# schematic1.net
KiCad netlist of a schematic drawn in Altium Designer
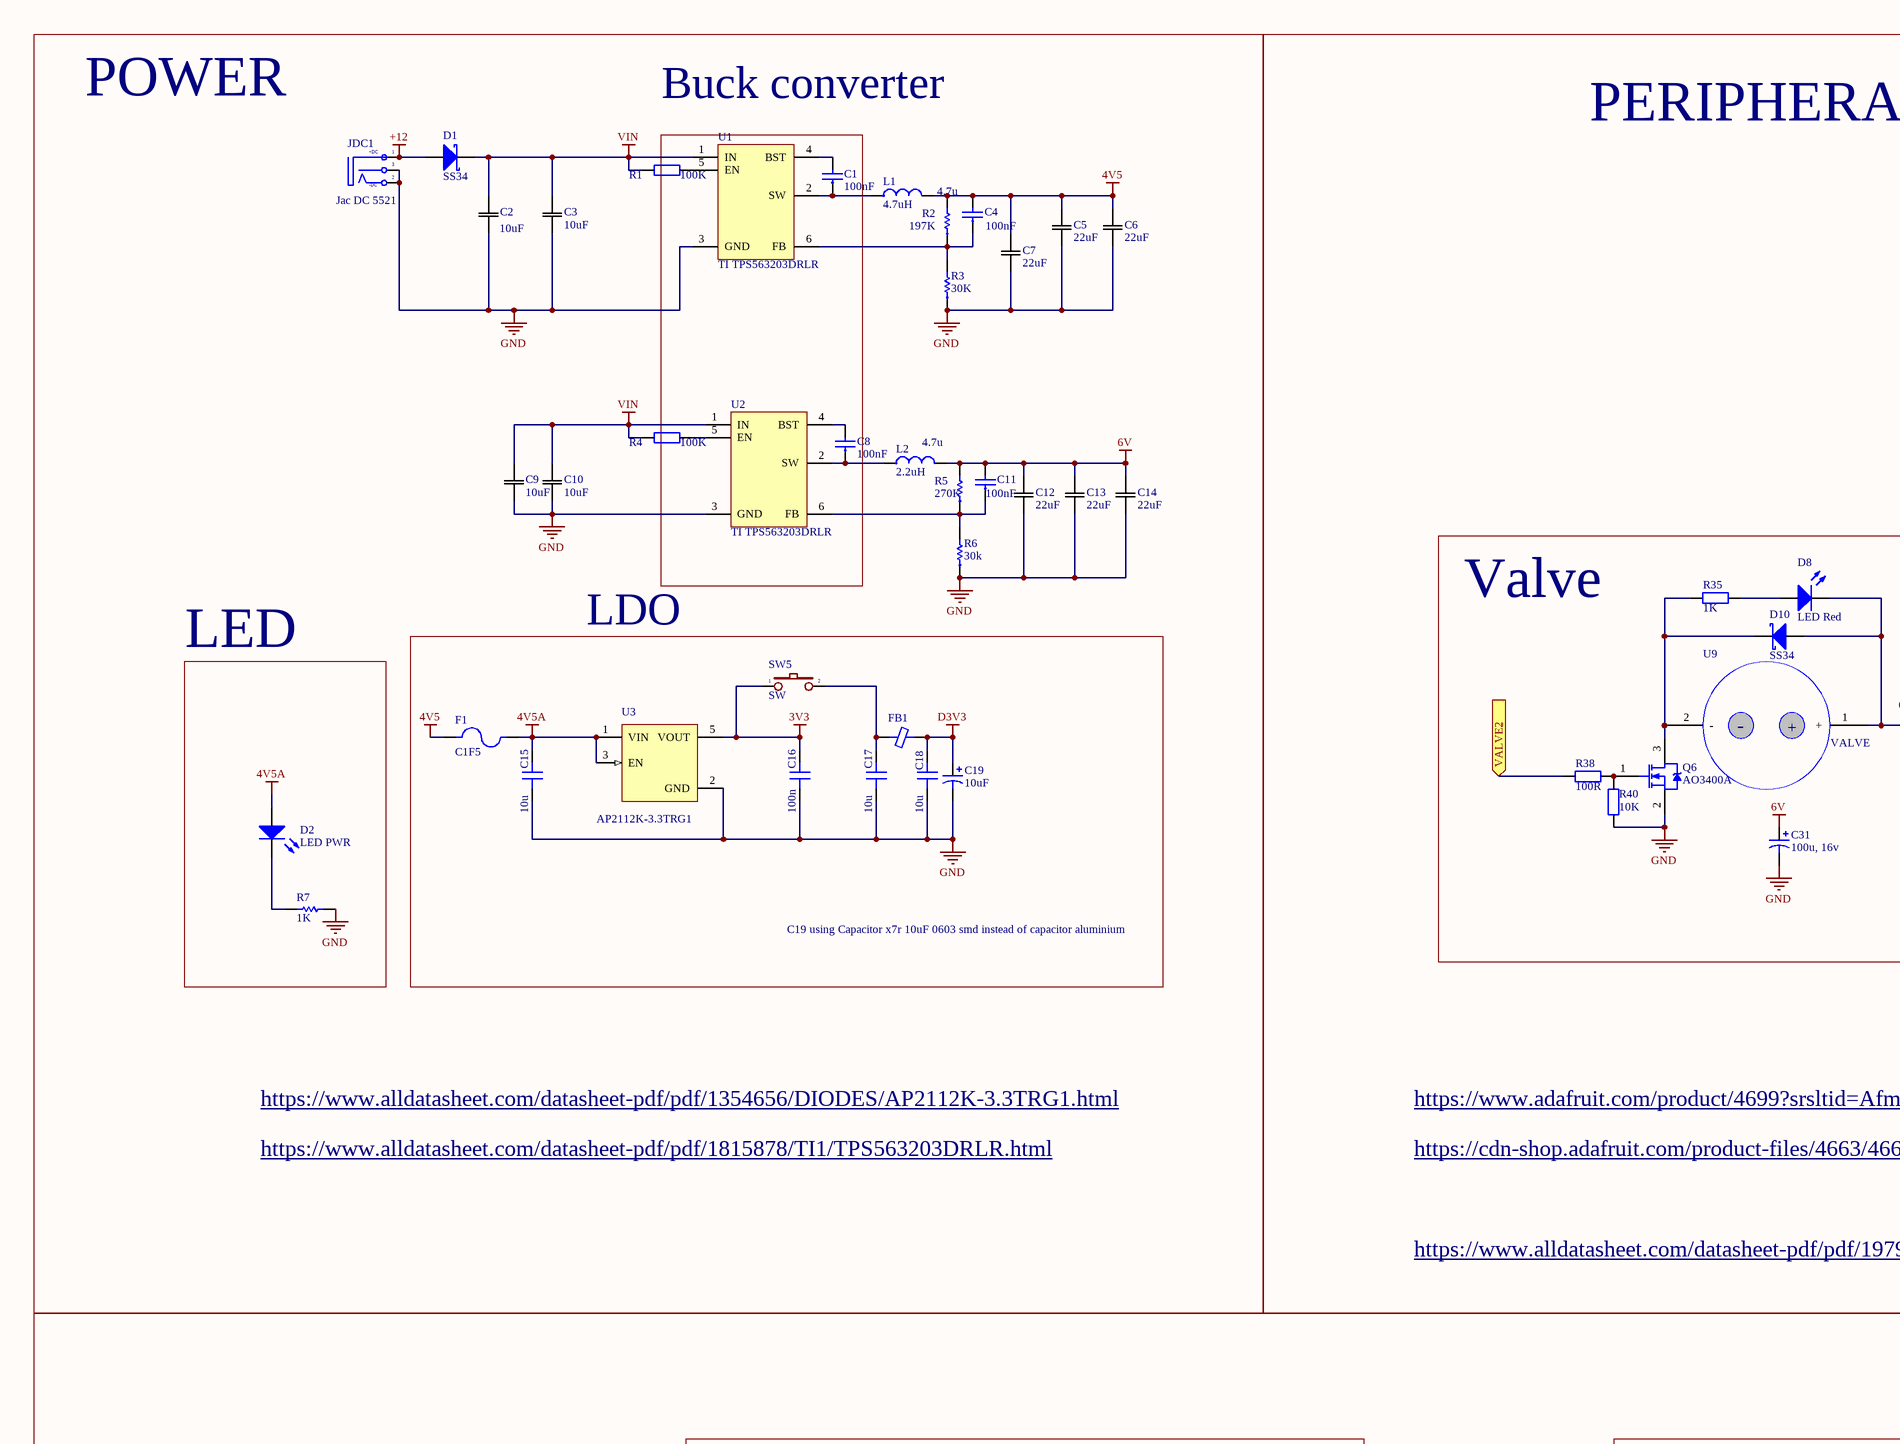
[diagram p0: schematic1.SchDoc, top left]
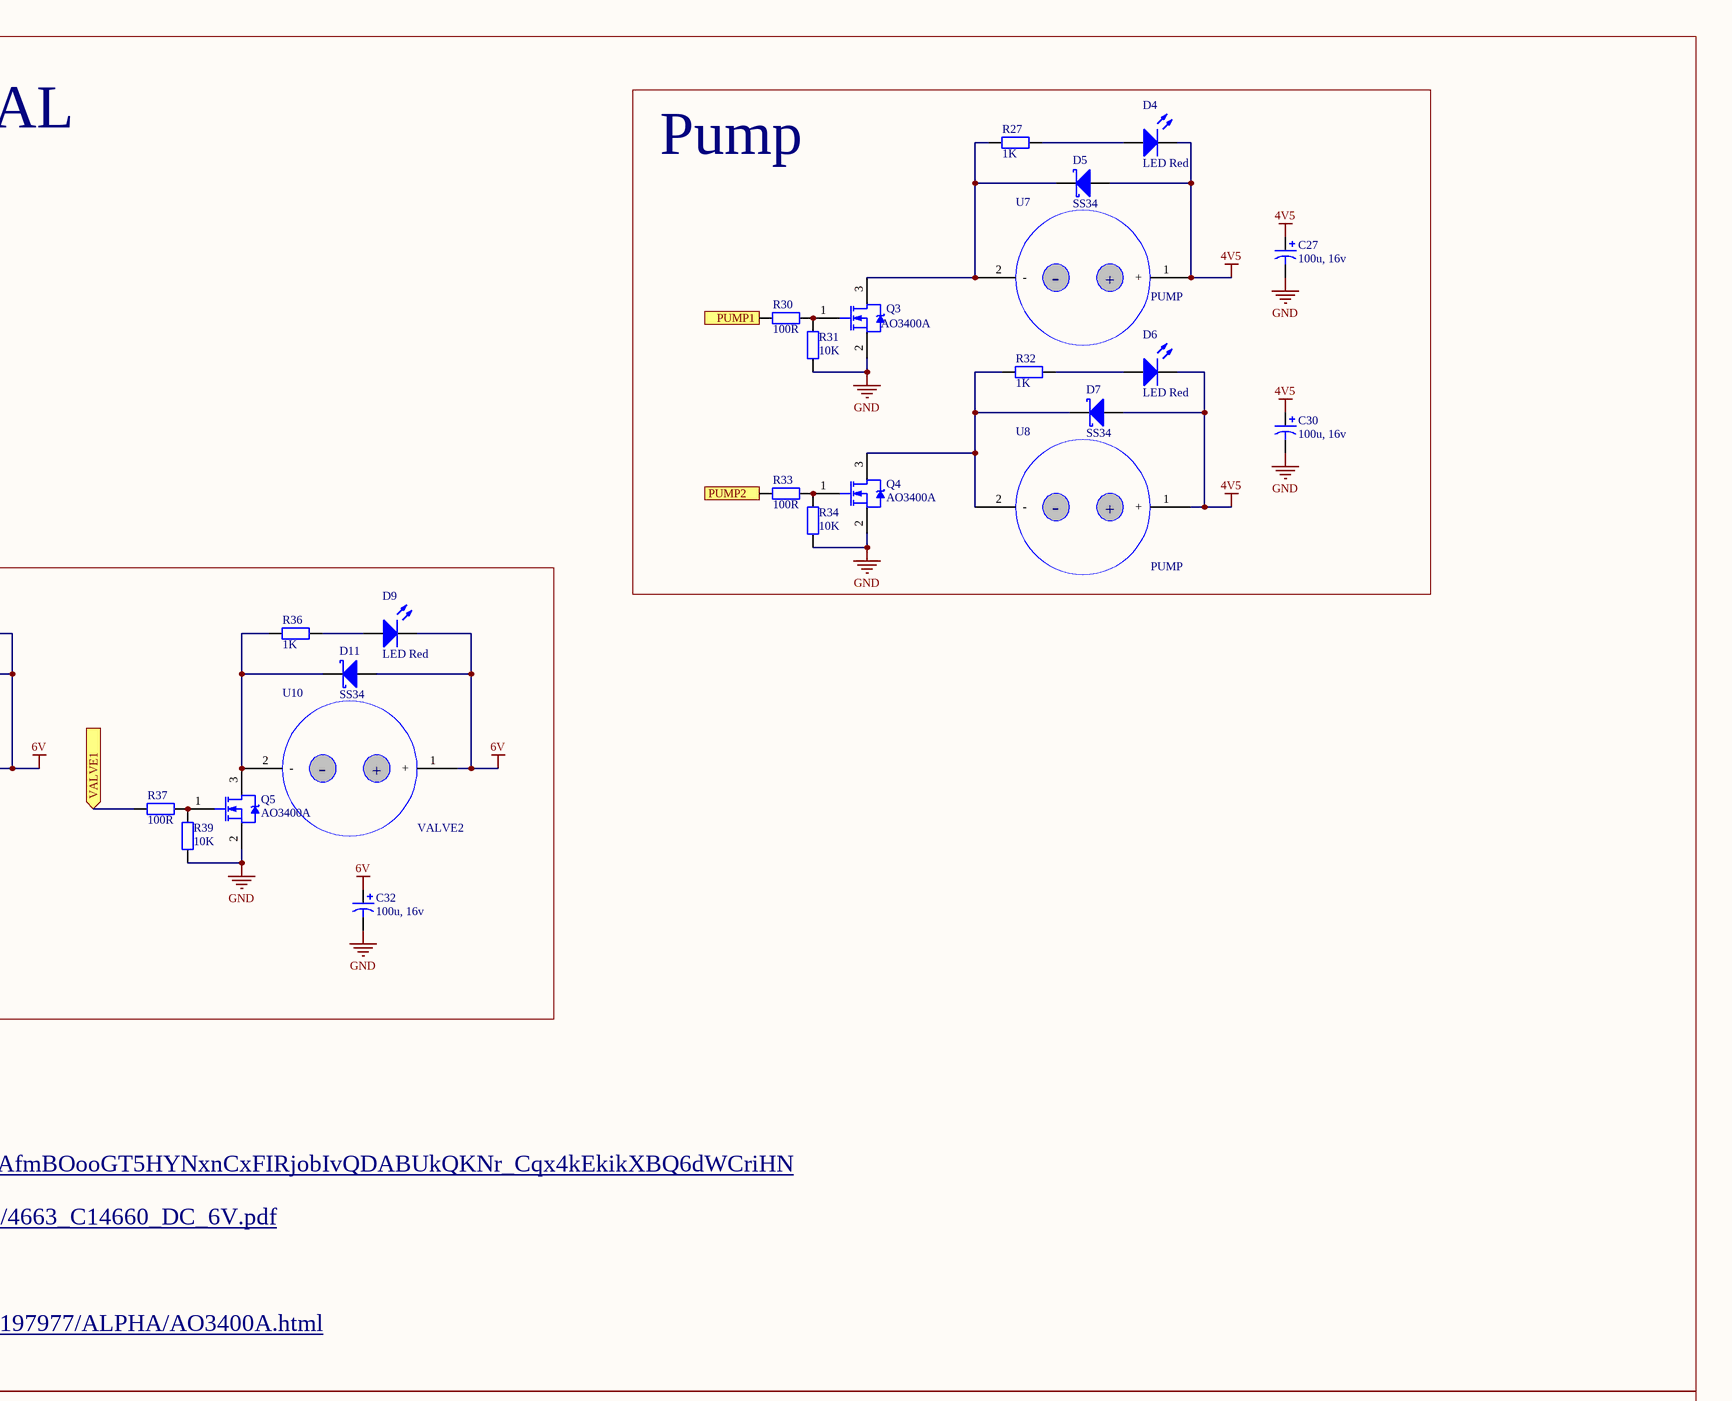
[diagram p1: schematic1.SchDoc, top right]
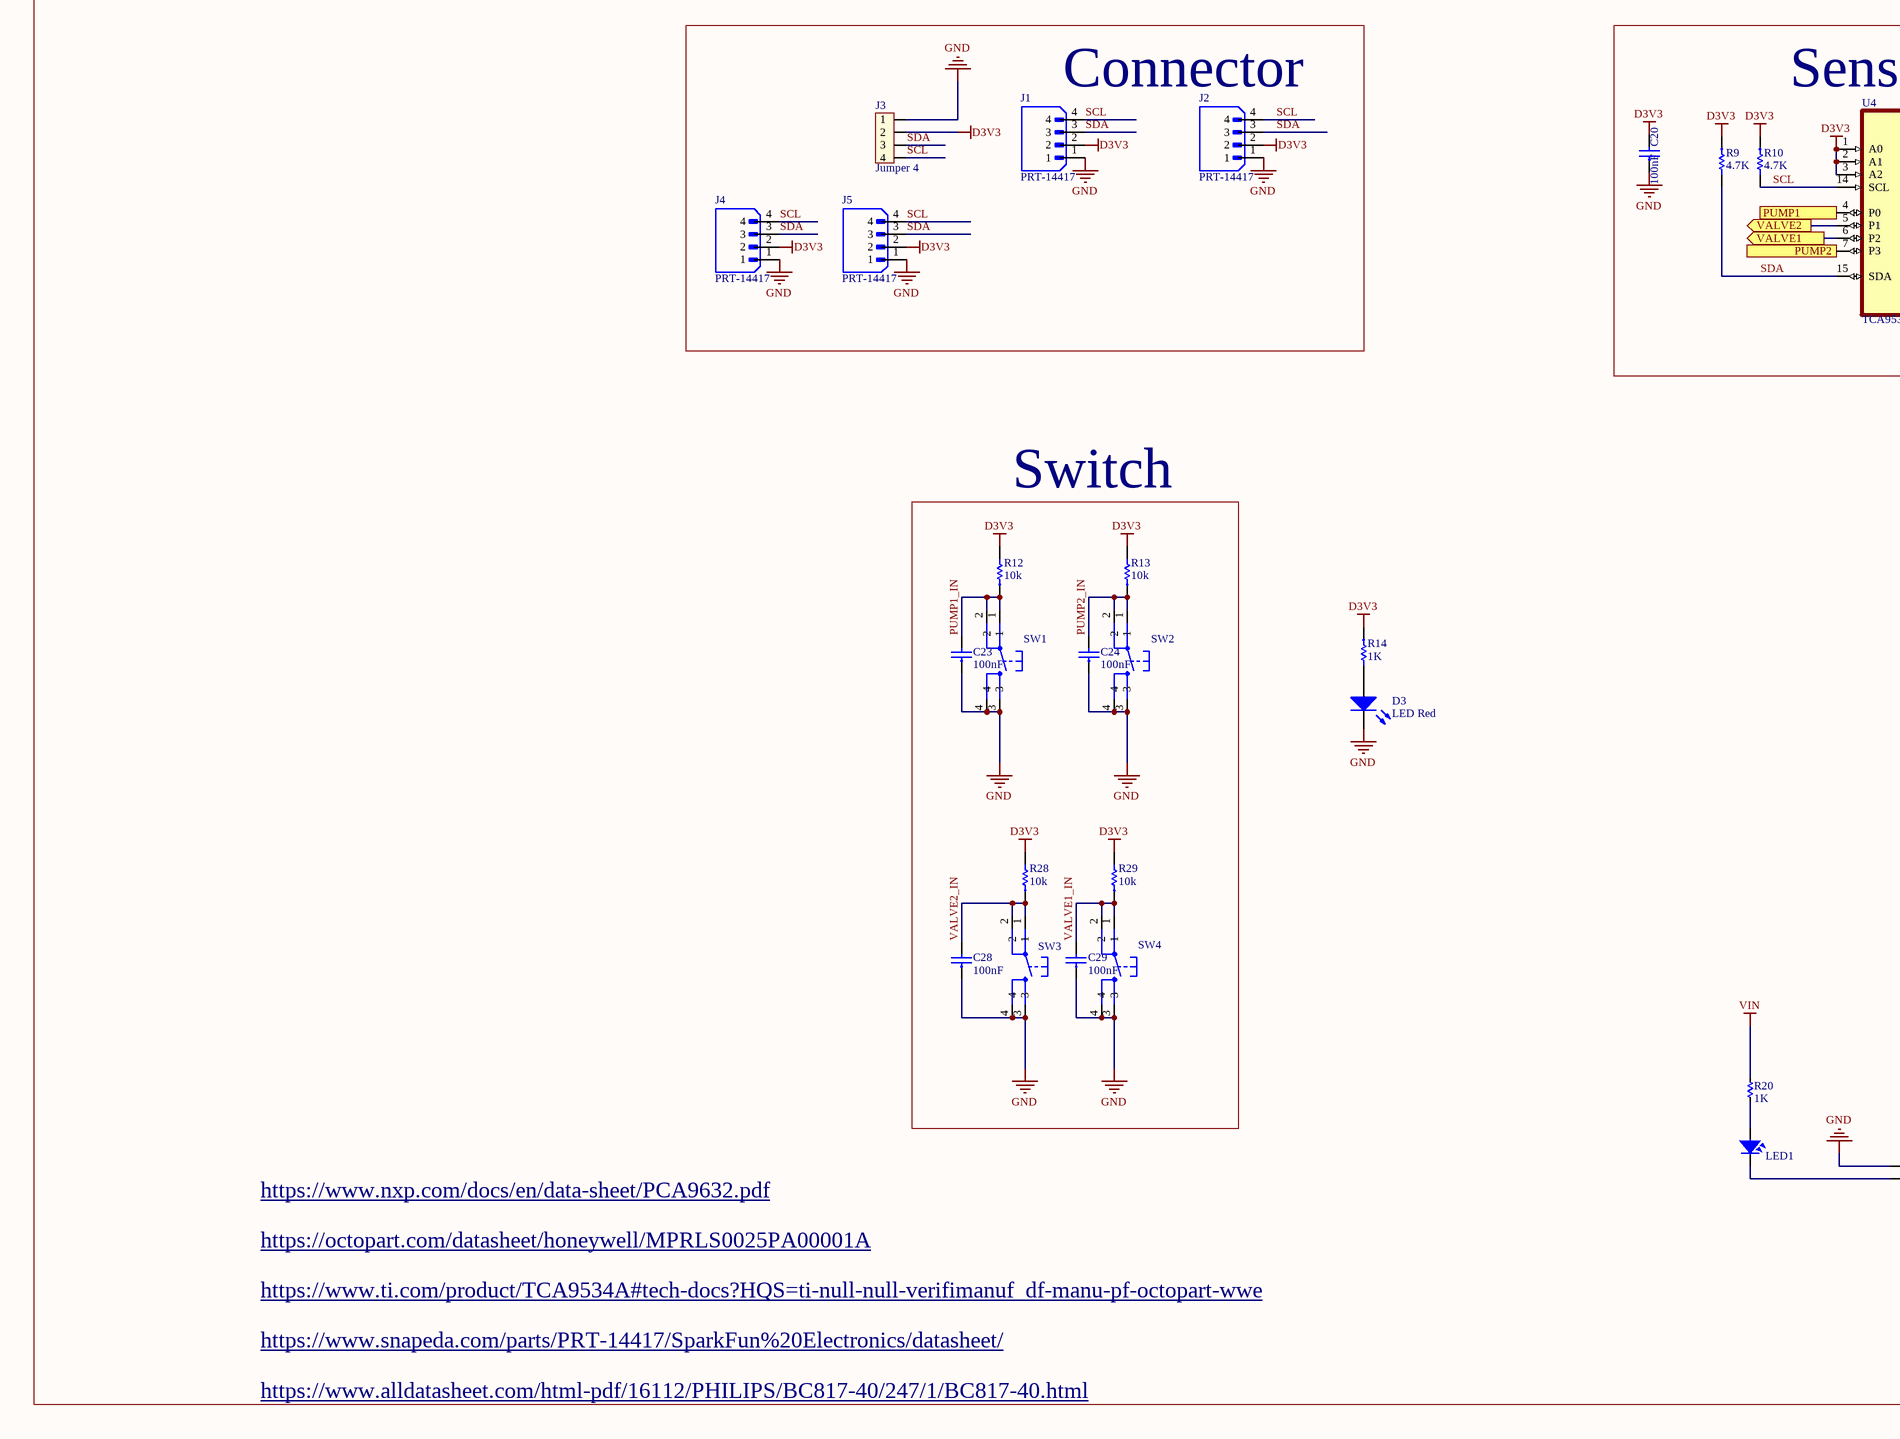
[diagram p2: schematic1.SchDoc, bottom left]
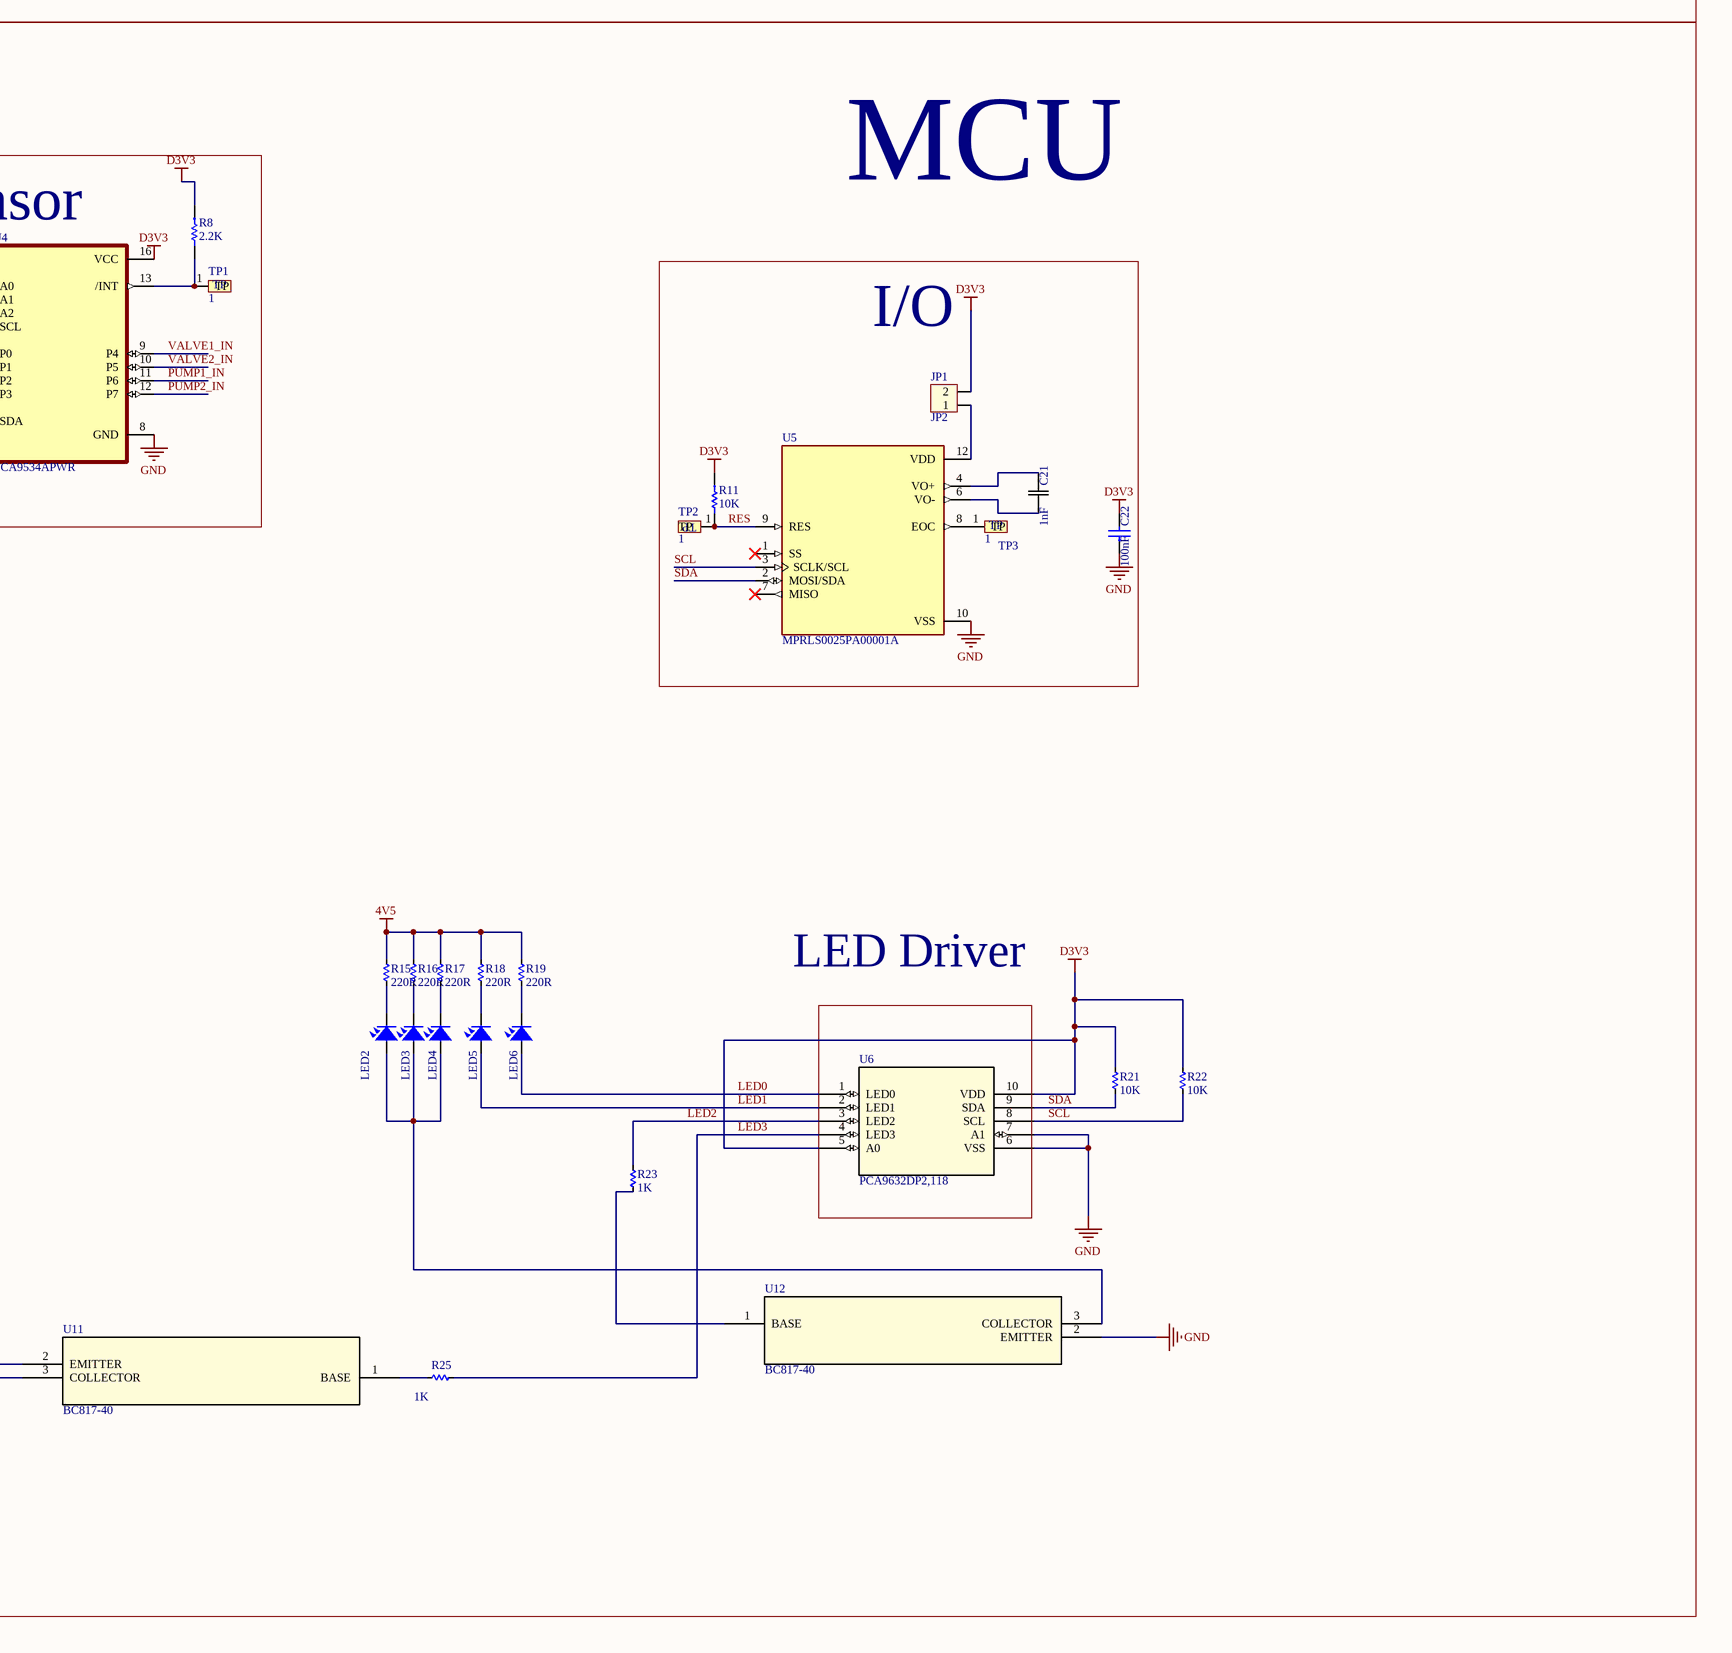
[diagram p3: schematic1.SchDoc, bottom right]

(export (version "E")
  (design (tool "Eeschema 10.0.6"))
  (components
    (comp (ref "C1")
      (value "100nF")
      (footprint "CN-SMD-0603")
      (description "CAP CER 100nF 10% 50V X7R 0603 SMD")
      (libsource (lib "2502-GMQLITE-MAIN") (part "CAPCER0001 100nF 10% 50V X7R 0603 SMD_1"))
    )
    (comp (ref "C2")
      (value "10uF")
      (footprint "CL10A106MQ8NNNC:CAP_CL10_SAM")
      (description "Description")
      (fields
        (field (name "MANUFACTURER_PART_NUMBER") "CL10A106MQ8NNNC")
        (field (name "COPYRIGHT") "Copyright (C) 2026 Ultra Librarian. All rights reserved.")
      )
      (libsource (lib "CL10A106MQ8NNNC") (part "CL10A106MQ8NNNC"))
    )
    (comp (ref "C3")
      (value "10uF")
      (footprint "CL10A106MQ8NNNC:CAP_CL10_SAM")
      (description "Description")
      (fields
        (field (name "MANUFACTURER_PART_NUMBER") "CL10A106MQ8NNNC")
        (field (name "COPYRIGHT") "Copyright (C) 2026 Ultra Librarian. All rights reserved.")
      )
      (libsource (lib "CL10A106MQ8NNNC") (part "CL10A106MQ8NNNC"))
    )
    (comp (ref "C4")
      (value "100nF")
      (footprint "CN-SMD-0603")
      (description "CAP CER 100nF 10% 50V X7R 0603 SMD")
      (libsource (lib "2502-GMQLITE-MAIN") (part "CAPCER0001 100nF 10% 50V X7R 0603 SMD"))
    )
    (comp (ref "C5")
      (value "22uF")
      (footprint "CN-SMD-0603")
      (description "Description")
      (fields
        (field (name "MANUFACTURER_PART_NUMBER") "GRM188R60J226MEA0D")
        (field (name "COPYRIGHT") "Copyright (C) 2026 Ultra Librarian. All rights reserved.")
      )
      (libsource (lib "GRM188R60J226MEA0D") (part "GRM188R60J226MEA0D"))
    )
    (comp (ref "C6")
      (value "22uF")
      (footprint "CN-SMD-0603")
      (description "Description")
      (fields
        (field (name "MANUFACTURER_PART_NUMBER") "GRM188R60J226MEA0D")
        (field (name "COPYRIGHT") "Copyright (C) 2026 Ultra Librarian. All rights reserved.")
      )
      (libsource (lib "GRM188R60J226MEA0D") (part "GRM188R60J226MEA0D"))
    )
    (comp (ref "C7")
      (value "22uF")
      (footprint "CN-SMD-0603")
      (description "Description")
      (fields
        (field (name "MANUFACTURER_PART_NUMBER") "GRM188R60J226MEA0D")
        (field (name "COPYRIGHT") "Copyright (C) 2026 Ultra Librarian. All rights reserved.")
      )
      (libsource (lib "GRM188R60J226MEA0D") (part "GRM188R60J226MEA0D"))
    )
    (comp (ref "C8")
      (value "100nF")
      (footprint "CN-SMD-0603")
      (description "CAP CER 100nF 10% 50V X7R 0603 SMD")
      (libsource (lib "2502-GMQLITE-MAIN") (part "CAPCER0001 100nF 10% 50V X7R 0603 SMD_1"))
    )
    (comp (ref "C9")
      (value "10uF")
      (footprint "CL10A106MQ8NNNC:CAP_CL10_SAM")
      (description "Description")
      (fields
        (field (name "MANUFACTURER_PART_NUMBER") "CL10A106MQ8NNNC")
        (field (name "COPYRIGHT") "Copyright (C) 2026 Ultra Librarian. All rights reserved.")
      )
      (libsource (lib "CL10A106MQ8NNNC") (part "CL10A106MQ8NNNC"))
    )
    (comp (ref "C10")
      (value "10uF")
      (footprint "CL10A106MQ8NNNC:CAP_CL10_SAM")
      (description "Description")
      (fields
        (field (name "MANUFACTURER_PART_NUMBER") "CL10A106MQ8NNNC")
        (field (name "COPYRIGHT") "Copyright (C) 2026 Ultra Librarian. All rights reserved.")
      )
      (libsource (lib "CL10A106MQ8NNNC") (part "CL10A106MQ8NNNC"))
    )
    (comp (ref "C11")
      (value "100nF")
      (footprint "CN-SMD-0603")
      (description "CAP CER 100nF 10% 50V X7R 0603 SMD")
      (libsource (lib "2502-GMQLITE-MAIN") (part "CAPCER0001 100nF 10% 50V X7R 0603 SMD"))
    )
    (comp (ref "C12")
      (value "22uF")
      (footprint "CN-SMD-0603")
      (description "Description")
      (fields
        (field (name "MANUFACTURER_PART_NUMBER") "GRM188R60J226MEA0D")
        (field (name "COPYRIGHT") "Copyright (C) 2026 Ultra Librarian. All rights reserved.")
      )
      (libsource (lib "GRM188R60J226MEA0D") (part "GRM188R60J226MEA0D"))
    )
    (comp (ref "C13")
      (value "22uF")
      (footprint "CN-SMD-0603")
      (description "Description")
      (fields
        (field (name "MANUFACTURER_PART_NUMBER") "GRM188R60J226MEA0D")
        (field (name "COPYRIGHT") "Copyright (C) 2026 Ultra Librarian. All rights reserved.")
      )
      (libsource (lib "GRM188R60J226MEA0D") (part "GRM188R60J226MEA0D"))
    )
    (comp (ref "C14")
      (value "22uF")
      (footprint "CN-SMD-0603")
      (description "Description")
      (fields
        (field (name "MANUFACTURER_PART_NUMBER") "GRM188R60J226MEA0D")
        (field (name "COPYRIGHT") "Copyright (C) 2026 Ultra Librarian. All rights reserved.")
      )
      (libsource (lib "GRM188R60J226MEA0D") (part "GRM188R60J226MEA0D"))
    )
    (comp (ref "C15")
      (value "10u")
      (footprint "CN-SMD-0603")
      (description "CAP0603 X7R 10UF 10% 10V")
      (fields
        (field (name "PART NUMBER") "GMC10X7R106K10NT")
        (field (name "MANUFACTURER") "Cal-Chip Electronics, Inc.")
      )
      (libsource (lib "Celestial Altium Library - altium_library") (part "Capacitor"))
    )
    (comp (ref "C16")
      (value "100n")
      (footprint "CN-SMD-0603")
      (description "CAP0603 X7R 100nF 10% 10V")
      (fields
        (field (name "PART NUMBER") "GMC10X7R106K10NT")
        (field (name "MANUFACTURER") "Cal-Chip Electronics, Inc.")
      )
      (libsource (lib "Celestial Altium Library - altium_library") (part "Capacitor"))
    )
    (comp (ref "C17")
      (value "10u")
      (footprint "CN-SMD-0603")
      (description "CAP0603 X7R 10UF 10% 10V")
      (fields
        (field (name "PART NUMBER") "GMC10X7R106K10NT")
        (field (name "MANUFACTURER") "Cal-Chip Electronics, Inc.")
      )
      (libsource (lib "Celestial Altium Library - altium_library") (part "Capacitor"))
    )
    (comp (ref "C18")
      (value "10u")
      (footprint "CN-SMD-0603")
      (description "CAP0603 X7R 10UF 10% 10V")
      (fields
        (field (name "PART NUMBER") "GMC10X7R106K10NT")
        (field (name "MANUFACTURER") "Cal-Chip Electronics, Inc.")
      )
      (libsource (lib "Celestial Altium Library - altium_library") (part "Capacitor"))
    )
    (comp (ref "C19")
      (value "10uF")
      (footprint "CN-SMD-0603")
      (description "CAP ALUM 100UF 20% \r\n16V SMD")
      (fields (field (name "Comment") "CAP ALUM 100UF 20% 16V SMD"))
      (libsource (lib "capacitor") (part "UWT1C101MCL1GB"))
    )
    (comp (ref "C20")
      (value "100nF")
      (footprint "CN-SMD-0603")
      (description "CAP CER 100nF 10% 50V X7R 0603 SMD")
      (libsource (lib "2502-GMQLITE-MAIN") (part "CAPCER0001 100nF 10% 50V X7R 0603 SMD"))
    )
    (comp (ref "C21")
      (value "1nF")
      (footprint "CN-SMD-0603")
      (description "No Description Available")
      (fields
        (field (name "MANUFACTURER_PART_NUMBER") "GCJ188R71H102KA01D")
        (field (name "COPYRIGHT") "Copyright (C) 2026 Ultra Librarian. All rights reserved.")
      )
      (libsource (lib "GCJ188R71H102KA01D") (part "GCJ188R71H102KA01D"))
    )
    (comp (ref "C22")
      (value "100nF")
      (footprint "CL10A106MQ8NNNC:CAP_CL10_SAM-L")
      (description "CAP CER 100nF 10% 50V X7R 0603 SMD")
      (libsource (lib "2502-GMQLITE-MAIN") (part "CAPCER0001 100nF 10% 50V X7R 0603 SMD"))
    )
    (comp (ref "C23")
      (value "100nF")
      (footprint "CN-SMD-0603")
      (description "CAP CER 100nF 10% 50V X7R 0603 SMD")
      (libsource (lib "2502-GMQLITE-MAIN") (part "CAPCER0001 100nF 10% 50V X7R 0603 SMD"))
    )
    (comp (ref "C24")
      (value "100nF")
      (footprint "CN-SMD-0603")
      (description "CAP CER 100nF 10% 50V X7R 0603 SMD")
      (libsource (lib "2502-GMQLITE-MAIN") (part "CAPCER0001 100nF 10% 50V X7R 0603 SMD"))
    )
    (comp (ref "C27")
      (value "100u, 16v")
      (footprint "CAP-ALU-SMD-D")
      (description "CAP ALUM 100UF 20% 16V SMD")
      (libsource (lib "capacitor") (part "UWT1C101MCL1GB"))
    )
    (comp (ref "C28")
      (value "100nF")
      (footprint "CN-SMD-0603")
      (description "CAP CER 100nF 10% 50V X7R 0603 SMD")
      (libsource (lib "2502-GMQLITE-MAIN") (part "CAPCER0001 100nF 10% 50V X7R 0603 SMD"))
    )
    (comp (ref "C29")
      (value "100nF")
      (footprint "CN-SMD-0603")
      (description "CAP CER 100nF 10% 50V X7R 0603 SMD")
      (libsource (lib "2502-GMQLITE-MAIN") (part "CAPCER0001 100nF 10% 50V X7R 0603 SMD"))
    )
    (comp (ref "C30")
      (value "100u, 16v")
      (footprint "CAP-ALU-SMD-D")
      (description "CAP ALUM 100UF 20% 16V SMD")
      (libsource (lib "capacitor") (part "UWT1C101MCL1GB"))
    )
    (comp (ref "C31")
      (value "100u, 16v")
      (footprint "CAP-ALU-SMD-D")
      (description "CAP ALUM 100UF 20% 16V SMD")
      (libsource (lib "capacitor") (part "UWT1C101MCL1GB"))
    )
    (comp (ref "C32")
      (value "100u, 16v")
      (footprint "CAP-ALU-SMD-D")
      (description "CAP ALUM 100UF 20% 16V SMD")
      (libsource (lib "capacitor") (part "UWT1C101MCL1GB"))
    )
    (comp (ref "D1")
      (value "SS34")
      (footprint "DIO-SMD-106")
      (description "Schottky Diode 40V 3A SMA")
      (libsource (lib "diode") (part "SS34"))
    )
    (comp (ref "D2")
      (value "LED PWR")
      (footprint "LED-0805-Red")
      (description "Lite-On LED Red 0603")
      (fields (field (name "Comment") "LED Red"))
      (libsource (lib "diode") (part "LTST-C190KRKT"))
    )
    (comp (ref "D3")
      (value "LED Red")
      (footprint "LED-0805-Red")
      (description "Lite-On LED Red 0603")
      (libsource (lib "diode") (part "LTST-C190KRKT"))
    )
    (comp (ref "D4")
      (value "LED Red")
      (footprint "LED-0805-Red")
      (description "Lite-On LED Red 0603")
      (libsource (lib "diode") (part "LTST-C190KRKT"))
    )
    (comp (ref "D5")
      (value "SS34")
      (footprint "DIO-SMD-106")
      (description "Schottky Diode 40V 3A SMA")
      (libsource (lib "diode") (part "SS34"))
    )
    (comp (ref "D6")
      (value "LED Red")
      (footprint "LED-0805-Red")
      (description "Lite-On LED Red 0603")
      (libsource (lib "diode") (part "LTST-C190KRKT"))
    )
    (comp (ref "D7")
      (value "SS34")
      (footprint "DIO-SMD-106")
      (description "Schottky Diode 40V 3A SMA")
      (libsource (lib "diode") (part "SS34"))
    )
    (comp (ref "D8")
      (value "LED Red")
      (footprint "LED-0805-Red")
      (description "Lite-On LED Red 0603")
      (libsource (lib "diode") (part "LTST-C190KRKT"))
    )
    (comp (ref "D9")
      (value "LED Red")
      (footprint "LED-0805-Red")
      (description "Lite-On LED Red 0603")
      (libsource (lib "diode") (part "LTST-C190KRKT"))
    )
    (comp (ref "D10")
      (value "SS34")
      (footprint "DIO-SMD-106")
      (description "Schottky Diode 40V 3A SMA")
      (libsource (lib "diode") (part "SS34"))
    )
    (comp (ref "D11")
      (value "SS34")
      (footprint "DIO-SMD-106")
      (description "Schottky Diode 40V 3A SMA")
      (libsource (lib "diode") (part "SS34"))
    )
    (comp (ref "F1")
      (value "C1F5")
      (footprint "RES-SMD-1206")
      (description "Fuse Chip Fast Acting 5A 125V SMD Solder Pad 1206 3.2 X 1.58 X 0.63mm")
      (fields (field (name "MANUFACTURER") "Bel TRP"))
      (libsource (lib "POWER_PIN_CAMERA") (part "C1F5"))
    )
    (comp (ref "FB1")
      (value "330")
      (footprint "IND_BLM18KG331WH1D_MUR-L")
      (description "FERRITE BEAD 330 OHM 0603 1LN")
      (fields
        (field (name "PART NUMBER") "BLM18KG331SH1D")
        (field (name "MANUFACTURER") "Murata Electronics")
      )
      (libsource (lib "Celestial Altium Library - altium_library") (part "Ferrite Chip"))
    )
    (comp (ref "J1")
      (value "PRT-14417")
      (footprint "SPARKFUN_PRT-14417")
      (description "QWIIC JST CONNECTOR - SMD 4-PIN")
      (fields (field (name "MF") "SparkFun Electronics"))
      (libsource (lib "PRT-14417") (part "PRT-14417"))
    )
    (comp (ref "J2")
      (value "PRT-14417")
      (footprint "SPARKFUN_PRT-14417")
      (description "QWIIC JST CONNECTOR - SMD 4-PIN")
      (fields (field (name "MF") "SparkFun Electronics"))
      (libsource (lib "PRT-14417") (part "PRT-14417"))
    )
    (comp (ref "J3")
      (value "Jumper 4")
      (footprint "JP4")
      (description "Jumper 3")
      (libsource (lib "hanguyen") (part "JP4"))
    )
    (comp (ref "J4")
      (value "PRT-14417")
      (footprint "SPARKFUN_PRT-14417")
      (description "QWIIC JST CONNECTOR - SMD 4-PIN")
      (fields (field (name "MF") "SparkFun Electronics"))
      (libsource (lib "PRT-14417") (part "PRT-14417"))
    )
    (comp (ref "J5")
      (value "PRT-14417")
      (footprint "SPARKFUN_PRT-14417")
      (description "QWIIC JST CONNECTOR - SMD 4-PIN")
      (fields (field (name "MF") "SparkFun Electronics"))
      (libsource (lib "PRT-14417") (part "PRT-14417"))
    )
    (comp (ref "JDC1")
      (value "Jac DC 5521")
      (footprint "DC0")
      (description "Jac DC input")
      (libsource (lib "2502-GMQLITE-MAIN") (part "DCIN"))
    )
    (comp (ref "JP1")
      (value "JP2")
      (footprint "JP2-CLOSED")
      (description "jumper 2.0 B")
      (libsource (lib "hanguyen") (part "Con2"))
    )
    (comp (ref "L1")
      (value "4.7uH")
      (footprint "Inductor_SMD")
      (description "IND MOI 1W2T 4.7uH 20% 5A 0420 SMD")
      (fields (field (name "ALTIUM_VALUE") "4.7u"))
      (libsource (lib "2502-GMQLITE-MAIN") (part "INDMOI0016 1W2T 2.2uH 20% 5A 0420 SMD"))
    )
    (comp (ref "L2")
      (value "2.2uH")
      (footprint "Inductor_SMD")
      (description "IND MOI 1W2T 4.7uH 20% 5A 0420 SMD")
      (fields (field (name "ALTIUM_VALUE") "4.7u"))
      (libsource (lib "2502-GMQLITE-MAIN") (part "INDMOI0016 1W2T 2.2uH 20% 5A 0420 SMD"))
    )
    (comp (ref "LED1")
      (value "LED")
      (footprint "LED-1206-Red")
      (description "LED Single colour Green and Red")
      (libsource (lib "Copy of KhanhBK_SCH_Library_1") (part "LED"))
    )
    (comp (ref "LED2")
      (value "LED")
      (footprint "LED-1206-Red")
      (description "LED Single colour Green and Red")
      (libsource (lib "Copy of KhanhBK_SCH_Library_1") (part "LED"))
    )
    (comp (ref "LED3")
      (value "LED")
      (footprint "LED-1206-Red")
      (description "LED Single colour Green and Red")
      (libsource (lib "Copy of KhanhBK_SCH_Library_1") (part "LED"))
    )
    (comp (ref "LED4")
      (value "LED")
      (footprint "LED-1206-Red")
      (description "LED Single colour Green and Red")
      (libsource (lib "Copy of KhanhBK_SCH_Library_1") (part "LED"))
    )
    (comp (ref "LED5")
      (value "LED")
      (footprint "LED-1206-Red")
      (description "LED Single colour Green and Red")
      (libsource (lib "Copy of KhanhBK_SCH_Library_1") (part "LED"))
    )
    (comp (ref "LED6")
      (value "LED")
      (footprint "LED-1206-Red")
      (description "LED Single colour Green and Red")
      (libsource (lib "Copy of KhanhBK_SCH_Library_1") (part "LED"))
    )
    (comp (ref "Q3")
      (value "AO3400A")
      (footprint "SOT-23-3L_AOS")
      (description "MOSFET N-CH 25V 5.8A SOT23")
      (libsource (lib "fet") (part "IRFML8244TRPBF"))
    )
    (comp (ref "Q4")
      (value "AO3400A")
      (footprint "SOT-23-3L_AOS-L")
      (description "MOSFET N-CH 25V 5.8A SOT23")
      (libsource (lib "fet") (part "IRFML8244TRPBF"))
    )
    (comp (ref "Q5")
      (value "AO3400A")
      (footprint "SOT-23-3L_AOS-L")
      (description "MOSFET N-CH 25V 5.8A SOT23")
      (libsource (lib "fet") (part "IRFML8244TRPBF"))
    )
    (comp (ref "Q6")
      (value "AO3400A")
      (footprint "SOT-23-3L_AOS-L")
      (description "MOSFET N-CH 25V 5.8A SOT23")
      (libsource (lib "fet") (part "IRFML8244TRPBF"))
    )
    (comp (ref "R1")
      (value "100K")
      (footprint "RES-SMD-0603")
      (description "Yageo RES 100K 5% 1/10W 0603")
      (fields (field (name "Comment") "RES 100K 5% 1/10W 0603"))
      (libsource (lib "resistor") (part "RC0603JR-07100KL"))
    )
    (comp (ref "R2")
      (value "197K")
      (footprint "RES-SMD-0603")
      (description "RES CHP 2K7 1% 1/10W 0603 SMD")
      (libsource (lib "2502-GMQLITE-MAIN") (part "RESCHP0195 2K7 1% 0603 SMD"))
    )
    (comp (ref "R3")
      (value "30K")
      (footprint "RES-SMD-0603")
      (description "RES CHP 2K7 1% 1/10W 0603 SMD")
      (libsource (lib "2502-GMQLITE-MAIN") (part "RESCHP0195 2K7 1% 0603 SMD"))
    )
    (comp (ref "R4")
      (value "100K")
      (footprint "RES-SMD-0603")
      (description "Yageo RES 100K 5% 1/10W 0603")
      (fields (field (name "Comment") "RES 100K 5% 1/10W 0603"))
      (libsource (lib "resistor") (part "RC0603JR-07100KL"))
    )
    (comp (ref "R5")
      (value "270K")
      (footprint "RES-SMD-0603")
      (description "RES CHP 2K7 1% 1/10W 0603 SMD")
      (libsource (lib "2502-GMQLITE-MAIN") (part "RESCHP0195 2K7 1% 0603 SMD"))
    )
    (comp (ref "R6")
      (value "30k")
      (footprint "RES-SMD-0603")
      (description "RES CHP 2K7 1% 1/10W 0603 SMD")
      (libsource (lib "2502-GMQLITE-MAIN") (part "RESCHP0195 2K7 1% 0603 SMD"))
    )
    (comp (ref "R7")
      (value "1K")
      (footprint "RES-SMD-0603")
      (description "Res Thick Film 0603 2.2K Ohm 5% 1/10W ±200ppm/°C Molded SMD SMD Paper T/R")
      (fields
        (field (name "MANUFACTURER") "Vishay")
        (field (name "MANUFACTURER PART NUMBER") "CRCW06032K20JNEA")
      )
      (libsource (lib "Stm32_Flyback_Driver_250814_1") (part "Resistor 2.2K"))
    )
    (comp (ref "R8")
      (value "2.2K")
      (footprint "RES-SMD-0603")
      (description "RES CHP 8K4 1% 1/10W 0603 SMD")
      (libsource (lib "2502-GMQLITE-MAIN") (part "RESCHP0428 8K4 1% 0603 SMD"))
    )
    (comp (ref "R9")
      (value "4.7K")
      (footprint "RES-SMD-0603")
      (description "RES CHP 8K4 1% 1/10W 0603 SMD")
      (libsource (lib "2502-GMQLITE-MAIN") (part "RESCHP0428 8K4 1% 0603 SMD"))
    )
    (comp (ref "R10")
      (value "4.7K")
      (footprint "RES-SMD-0603")
      (description "RES CHP 8K4 1% 1/10W 0603 SMD")
      (libsource (lib "2502-GMQLITE-MAIN") (part "RESCHP0428 8K4 1% 0603 SMD"))
    )
    (comp (ref "R11")
      (value "10K")
      (footprint "RES-SMD-0603")
      (description "RES CHP 8K4 1% 1/10W 0603 SMD")
      (libsource (lib "2502-GMQLITE-MAIN") (part "RESCHP0428 8K4 1% 0603 SMD"))
    )
    (comp (ref "R12")
      (value "10k")
      (footprint "RES-SMD-0603")
      (description "RES CHP 8K4 1% 1/10W 0603 SMD")
      (libsource (lib "2502-GMQLITE-MAIN") (part "RESCHP0428 8K4 1% 0603 SMD"))
    )
    (comp (ref "R13")
      (value "10k")
      (footprint "RES-SMD-0603")
      (description "RES CHP 8K4 1% 1/10W 0603 SMD")
      (libsource (lib "2502-GMQLITE-MAIN") (part "RESCHP0428 8K4 1% 0603 SMD"))
    )
    (comp (ref "R14")
      (value "1K")
      (footprint "RES-SMD-0603")
      (description "RES CHP 8K4 1% 1/10W 0603 SMD")
      (libsource (lib "2502-GMQLITE-MAIN") (part "RESCHP0428 8K4 1% 0603 SMD"))
    )
    (comp (ref "R15")
      (value "220R")
      (footprint "RES-SMD-0603")
      (description "Resistor")
      (fields
        (field (name "MANUFACTURER") "Generic Components")
        (field (name "PUBLISHER") "Altium Hobart Technology Centre")
      )
      (libsource (lib "Copy of KhanhBK_SCH_Library_1") (part "Res-SMD"))
    )
    (comp (ref "R16")
      (value "220R")
      (footprint "RES-SMD-0603")
      (description "Resistor")
      (fields
        (field (name "MANUFACTURER") "Generic Components")
        (field (name "PUBLISHER") "Altium Hobart Technology Centre")
      )
      (libsource (lib "Copy of KhanhBK_SCH_Library_1") (part "Res-SMD"))
    )
    (comp (ref "R17")
      (value "220R")
      (footprint "RES-SMD-0603")
      (description "Resistor")
      (fields
        (field (name "MANUFACTURER") "Generic Components")
        (field (name "PUBLISHER") "Altium Hobart Technology Centre")
      )
      (libsource (lib "Copy of KhanhBK_SCH_Library_1") (part "Res-SMD"))
    )
    (comp (ref "R18")
      (value "220R")
      (footprint "RES-SMD-0603")
      (description "Resistor")
      (fields
        (field (name "MANUFACTURER") "Generic Components")
        (field (name "PUBLISHER") "Altium Hobart Technology Centre")
      )
      (libsource (lib "Copy of KhanhBK_SCH_Library_1") (part "Res-SMD"))
    )
    (comp (ref "R19")
      (value "220R")
      (footprint "RES-SMD-0603")
      (description "Resistor")
      (fields
        (field (name "MANUFACTURER") "Generic Components")
        (field (name "PUBLISHER") "Altium Hobart Technology Centre")
      )
      (libsource (lib "Copy of KhanhBK_SCH_Library_1") (part "Res-SMD"))
    )
    (comp (ref "R20")
      (value "1K")
      (footprint "RES-SMD-0603")
      (description "Resistor")
      (fields
        (field (name "MANUFACTURER") "Generic Components")
        (field (name "PUBLISHER") "Altium Hobart Technology Centre")
      )
      (libsource (lib "Copy of KhanhBK_SCH_Library_1") (part "Res-SMD"))
    )
    (comp (ref "R21")
      (value "10K")
      (footprint "RES-SMD-0603")
      (description "Resistor")
      (fields
        (field (name "MANUFACTURER") "Generic Components")
        (field (name "PUBLISHER") "Altium Hobart Technology Centre")
      )
      (libsource (lib "Copy of KhanhBK_SCH_Library_1") (part "Res-SMD"))
    )
    (comp (ref "R22")
      (value "10K")
      (footprint "RES-SMD-0603")
      (description "Resistor")
      (fields
        (field (name "MANUFACTURER") "Generic Components")
        (field (name "PUBLISHER") "Altium Hobart Technology Centre")
      )
      (libsource (lib "Copy of KhanhBK_SCH_Library_1") (part "Res-SMD"))
    )
    (comp (ref "R23")
      (value "1K")
      (footprint "RES-SMD-0603")
      (description "Resistor")
      (fields
        (field (name "MANUFACTURER") "Generic Components")
        (field (name "PUBLISHER") "Altium Hobart Technology Centre")
      )
      (libsource (lib "Copy of KhanhBK_SCH_Library_1") (part "Res-SMD"))
    )
    (comp (ref "R25")
      (value "1K")
      (footprint "RES-SMD-0603")
      (description "Resistor")
      (fields
        (field (name "MANUFACTURER") "Generic Components")
        (field (name "PUBLISHER") "Altium Hobart Technology Centre")
      )
      (libsource (lib "Copy of KhanhBK_SCH_Library_1") (part "Res-SMD"))
    )
    (comp (ref "R27")
      (value "1K")
      (footprint "RES-SMD-0603")
      (description "Yageo RES 1K 5% 1/10W 0603")
      (fields (field (name "Comment") "RES 1K 5% 1/10W 0603"))
      (libsource (lib "resistor") (part "RC0603JR-071KL"))
    )
    (comp (ref "R28")
      (value "10k")
      (footprint "RES-SMD-0603")
      (description "RES CHP 8K4 1% 1/10W 0603 SMD")
      (libsource (lib "2502-GMQLITE-MAIN") (part "RESCHP0428 8K4 1% 0603 SMD"))
    )
    (comp (ref "R29")
      (value "10k")
      (footprint "RES-SMD-0603")
      (description "RES CHP 8K4 1% 1/10W 0603 SMD")
      (libsource (lib "2502-GMQLITE-MAIN") (part "RESCHP0428 8K4 1% 0603 SMD"))
    )
    (comp (ref "R30")
      (value "100R")
      (footprint "RES-SMD-0603")
      (description "Yageo RES 100R 5% 1/10W 0603")
      (fields (field (name "Comment") "RES 100R 5% 1/10W 0603"))
      (libsource (lib "resistor") (part "RC0603JR-07100RL"))
    )
    (comp (ref "R31")
      (value "10K")
      (footprint "RES-SMD-0603")
      (description "Yageo RES 10K 5% 1/10W 0603")
      (fields (field (name "Comment") "RES 10K 5% 1/10W 0603"))
      (libsource (lib "resistor") (part "RC0603JR-0710KL"))
    )
    (comp (ref "R32")
      (value "1K")
      (footprint "RES-SMD-0603")
      (description "Yageo RES 1K 5% 1/10W 0603")
      (fields (field (name "Comment") "RES 1K 5% 1/10W 0603"))
      (libsource (lib "resistor") (part "RC0603JR-071KL"))
    )
    (comp (ref "R33")
      (value "100R")
      (footprint "RES-SMD-0603")
      (description "Yageo RES 100R 5% 1/10W 0603")
      (fields (field (name "Comment") "RES 100R 5% 1/10W 0603"))
      (libsource (lib "resistor") (part "RC0603JR-07100RL"))
    )
    (comp (ref "R34")
      (value "10K")
      (footprint "RES-SMD-0603")
      (description "Yageo RES 10K 5% 1/10W 0603")
      (fields (field (name "Comment") "RES 10K 5% 1/10W 0603"))
      (libsource (lib "resistor") (part "RC0603JR-0710KL"))
    )
    (comp (ref "R35")
      (value "1K")
      (footprint "RES-SMD-0603")
      (description "Yageo RES 1K 5% 1/10W 0603")
      (fields (field (name "Comment") "RES 1K 5% 1/10W 0603"))
      (libsource (lib "resistor") (part "RC0603JR-071KL"))
    )
    (comp (ref "R36")
      (value "1K")
      (footprint "RES-SMD-0603")
      (description "Yageo RES 1K 5% 1/10W 0603")
      (fields (field (name "Comment") "RES 1K 5% 1/10W 0603"))
      (libsource (lib "resistor") (part "RC0603JR-071KL"))
    )
    (comp (ref "R37")
      (value "100R")
      (footprint "RES-SMD-0603")
      (description "Yageo RES 100R 5% 1/10W 0603")
      (fields (field (name "Comment") "RES 100R 5% 1/10W 0603"))
      (libsource (lib "resistor") (part "RC0603JR-07100RL"))
    )
    (comp (ref "R38")
      (value "100R")
      (footprint "RES-SMD-0603")
      (description "Yageo RES 100R 5% 1/10W 0603")
      (fields (field (name "Comment") "RES 100R 5% 1/10W 0603"))
      (libsource (lib "resistor") (part "RC0603JR-07100RL"))
    )
    (comp (ref "R39")
      (value "10K")
      (footprint "RES-SMD-0603")
      (description "Yageo RES 10K 5% 1/10W 0603")
      (fields (field (name "Comment") "RES 10K 5% 1/10W 0603"))
      (libsource (lib "resistor") (part "RC0603JR-0710KL"))
    )
    (comp (ref "R40")
      (value "10K")
      (footprint "RES-SMD-0603")
      (description "Yageo RES 10K 5% 1/10W 0603")
      (fields (field (name "Comment") "RES 10K 5% 1/10W 0603"))
      (libsource (lib "resistor") (part "RC0603JR-0710KL"))
    )
    (comp (ref "SW1")
      (value "SW2")
      (footprint "SW2-DIP")
      (description "Switch button 4 pin")
      (libsource (lib "Stm32_Flyback_Driver_250814_1") (part "SW2"))
    )
    (comp (ref "SW2")
      (value "SW2")
      (footprint "SW2-DIP")
      (description "Switch button 4 pin")
      (libsource (lib "Stm32_Flyback_Driver_250814_1") (part "SW2"))
    )
    (comp (ref "SW3")
      (value "SW2")
      (footprint "SW2-DIP")
      (description "Switch button 4 pin")
      (libsource (lib "Stm32_Flyback_Driver_250814_1") (part "SW2"))
    )
    (comp (ref "SW4")
      (value "SW2")
      (footprint "SW2-DIP")
      (description "Switch button 4 pin")
      (libsource (lib "Stm32_Flyback_Driver_250814_1") (part "SW2"))
    )
    (comp (ref "SW5")
      (value "SW")
      (footprint "SW-DIP1")
      (description "Switch button 2 pin")
      (libsource (lib "Altium Library") (part "SW2"))
    )
    (comp (ref "TP1")
      (value "1")
      (footprint "TP - 2")
      (description "CONNECT 1")
      (libsource (lib "hanguyen") (part "TP"))
    )
    (comp (ref "TP2")
      (value "1")
      (footprint "TP - 2")
      (description "CONNECT 1")
      (libsource (lib "") (part "TP_1"))
    )
    (comp (ref "TP3")
      (value "1")
      (footprint "TP - 2")
      (description "CONNECT 1")
      (libsource (lib "hanguyen") (part "TP"))
    )
    (comp (ref "U1")
      (value "TI TPS563203DRLR")
      (footprint "SOT50P160X60-6N:SOT50P160X60-6N")
      (description "ICS OCV BCK TPS563201 3A SOT23-6 SMD")
      (libsource (lib "2502-GMQLITE-MAIN") (part "ICSOCV0021 BCK TPS563201 3A SOT23-6 SMD"))
    )
    (comp (ref "U2")
      (value "TI TPS563203DRLR")
      (footprint "SOT50P160X60-6N:SOT50P160X60-6N")
      (description "ICS OCV BCK TPS563201 3A SOT23-6 SMD")
      (libsource (lib "2502-GMQLITE-MAIN") (part "ICSOCV0021 BCK TPS563201 3A SOT23-6 SMD"))
    )
    (comp (ref "U3")
      (value "AP2112K-3.3TRG1")
      (footprint "AP2112K-3P3TRG1:SOT_RG1_DIO")
      (description "AP2112 Series 0.6 A 3.3 V Fixed Output SMT LDO Linear Regulator - SOT23-5")
      (fields (field (name "MF") "Diodes Inc."))
      (libsource (lib "hanguyen") (part "AP2112K-3.3TRG1"))
    )
    (comp (ref "U4")
      (value "TCA9534APWR")
      (footprint "SOP65P640X120-16N")
      (description "8-bit 1.65- to 5.5-V I2C/SMBus I/O expander with interrupt, & config registers")
      (fields (field (name "MF") "Texas Instruments"))
      (libsource (lib "TCA9534APWR") (part "TCA9534APWR"))
    )
    (comp (ref "U5")
      (value "MPRLS0025PA00001A")
      (footprint "SnapEDApcb:XDCR_MPRLS0025PA00001A")
      (description "Pressure Sensor 25PSI _172.37kPa_ Absolute Male - 0.1 _2.5mm_ Tube 24 b 12-SMD Module")
      (fields (field (name "DIGI-KEY_PART_NUMBER") "480-7098-1-ND") (field (name "MF") "Honeywell Sensing"))
      (libsource (lib "SnapEDAsch") (part "MPRLS0025PA00001A"))
    )
    (comp (ref "U6")
      (value "PCA9632DP2,118")
      (footprint "TSSOP10_3P1X3P1_NXP")
      (description "No Description Available")
      (fields (field (name "COPYRIGHT") "Copyright (C) 2026 Ultra Librarian. All rights reserved."))
      (libsource (lib "PCA9632DP2,118") (part "PCA9632DP2,118"))
    )
    (comp (ref "U7")
      (value "PUMP")
      (footprint "Pump")
      (description "Connector Header 2 Position 6.35mm Solder Straight Thru-Hole 2 Terminal 1 Port MLX-Series")
      (fields (field (name "MANUFACTURER") "Molex") (field (name "MANUFACTURER PART NUMBER") "10-84-4022"))
      (libsource (lib "LIB_PRESSURE") (part "A5F083"))
    )
    (comp (ref "U8")
      (value "PUMP")
      (footprint "Pump")
      (description "Connector Header 2 Position 6.35mm Solder Straight Thru-Hole 2 Terminal 1 Port MLX-Series")
      (fields (field (name "MANUFACTURER") "Molex") (field (name "MANUFACTURER PART NUMBER") "10-84-4022"))
      (libsource (lib "LIB_PRESSURE") (part "A5F083"))
    )
    (comp (ref "U9")
      (value "VALVE")
      (footprint "VALVE")
      (description "Connector Header 2 Position 6.35mm Solder Straight Thru-Hole 2 Terminal 1 Port MLX-Series")
      (fields (field (name "MANUFACTURER") "Molex") (field (name "MANUFACTURER PART NUMBER") "10-84-4022"))
      (libsource (lib "LIB_PRESSURE") (part "A5F083"))
    )
    (comp (ref "U10")
      (value "VALVE2")
      (footprint "VALVE")
      (description "Connector Header 2 Position 6.35mm Solder Straight Thru-Hole 2 Terminal 1 Port MLX-Series")
      (fields (field (name "MANUFACTURER") "Molex") (field (name "MANUFACTURER PART NUMBER") "10-84-4022"))
      (libsource (lib "LIB_PRESSURE") (part "A5F083"))
    )
    (comp (ref "U11")
      (value "BC817-40")
      (footprint "SOT23_NEX")
      (description "No Description Available")
      (fields (field (name "COPYRIGHT") "Copyright (C) 2026 Ultra Librarian. All rights reserved."))
      (libsource (lib "") (part "BC817-40_1"))
    )
    (comp (ref "U12")
      (value "BC817-40")
      (footprint "SOT23_NEX")
      (description "No Description Available")
      (fields (field (name "COPYRIGHT") "Copyright (C) 2026 Ultra Librarian. All rights reserved."))
      (libsource (lib "BC817-40") (part "BC817-40"))
    )
  )
  (nets
    (net (code "1") (name "+12") (class "Default")
      (node (ref "D1") (pin "1") (pinfunction "A_1") (pintype "passive"))
      (node (ref "JDC1") (pin "1") (pinfunction "T_1") (pintype "passive"))
    )
    (net (code "2") (name "/LED0") (class "Default")
      (node (ref "LED6") (pin "1") (pinfunction "1_1") (pintype "passive"))
      (node (ref "U6") (pin "1") (pinfunction "LED0_1") (pintype "bidirectional"))
    )
    (net (code "3") (name "/LED1") (class "Default")
      (node (ref "LED5") (pin "1") (pinfunction "1_1") (pintype "passive"))
      (node (ref "U6") (pin "2") (pinfunction "LED1_2") (pintype "bidirectional"))
    )
    (net (code "4") (name "/LED2") (class "Default")
      (node (ref "R23") (pin "2") (pinfunction "2_2") (pintype "passive"))
      (node (ref "U6") (pin "3") (pinfunction "LED2_3") (pintype "bidirectional"))
    )
    (net (code "5") (name "/LED3") (class "Default")
      (node (ref "R25") (pin "1") (pinfunction "1_1") (pintype "passive"))
      (node (ref "U6") (pin "4") (pinfunction "LED3_4") (pintype "bidirectional"))
    )
    (net (code "6") (name "/PUMP1") (class "Default")
      (node (ref "R30") (pin "1") (pinfunction "1_1") (pintype "passive"))
      (node (ref "U4") (pin "4") (pinfunction "P0_4") (pintype "bidirectional"))
    )
    (net (code "7") (name "/PUMP1_IN") (class "Default")
      (node (ref "C23") (pin "2") (pinfunction "2_2") (pintype "passive"))
      (node (ref "R12") (pin "1") (pinfunction "1_1") (pintype "passive"))
      (node (ref "SW1") (pin "1") (pinfunction "1_1") (pintype "passive"))
      (node (ref "SW1") (pin "2") (pinfunction "2_2") (pintype "passive"))
      (node (ref "U4") (pin "11") (pinfunction "P6_11") (pintype "bidirectional"))
    )
    (net (code "8") (name "/PUMP2") (class "Default")
      (node (ref "R33") (pin "1") (pinfunction "1_1") (pintype "passive"))
      (node (ref "U4") (pin "7") (pinfunction "P3_7") (pintype "bidirectional"))
    )
    (net (code "9") (name "/PUMP2_IN") (class "Default")
      (node (ref "C24") (pin "2") (pinfunction "2_2") (pintype "passive"))
      (node (ref "R13") (pin "1") (pinfunction "1_1") (pintype "passive"))
      (node (ref "SW2") (pin "1") (pinfunction "1_1") (pintype "passive"))
      (node (ref "SW2") (pin "2") (pinfunction "2_2") (pintype "passive"))
      (node (ref "U4") (pin "12") (pinfunction "P7_12") (pintype "bidirectional"))
    )
    (net (code "10") (name "/RES") (class "Default")
      (node (ref "R11") (pin "2") (pinfunction "2_2") (pintype "passive"))
      (node (ref "TP2") (pin "1") (pinfunction "TP_1") (pintype "passive"))
      (node (ref "U5") (pin "9") (pinfunction "RES_9") (pintype "input"))
    )
    (net (code "11") (name "/SCL") (class "Default")
      (node (ref "J1") (pin "4") (pinfunction "4_4") (pintype "passive"))
      (node (ref "J2") (pin "4") (pinfunction "4_4") (pintype "passive"))
      (node (ref "J3") (pin "4") (pinfunction "4_4") (pintype "passive"))
      (node (ref "J4") (pin "4") (pinfunction "4_4") (pintype "passive"))
      (node (ref "J5") (pin "4") (pinfunction "4_4") (pintype "passive"))
      (node (ref "R10") (pin "2") (pinfunction "2_2") (pintype "passive"))
      (node (ref "R22") (pin "2") (pinfunction "2_2") (pintype "passive"))
      (node (ref "U4") (pin "14") (pinfunction "SCL_14") (pintype "input"))
      (node (ref "U5") (pin "3") (pinfunction "SCLK/SCL_3") (pintype "input"))
      (node (ref "U6") (pin "8") (pinfunction "SCL_8") (pintype "passive"))
    )
    (net (code "12") (name "/SDA") (class "Default")
      (node (ref "J1") (pin "3") (pinfunction "3_3") (pintype "passive"))
      (node (ref "J2") (pin "3") (pinfunction "3_3") (pintype "passive"))
      (node (ref "J3") (pin "3") (pinfunction "3_3") (pintype "passive"))
      (node (ref "J4") (pin "3") (pinfunction "3_3") (pintype "passive"))
      (node (ref "J5") (pin "3") (pinfunction "3_3") (pintype "passive"))
      (node (ref "R21") (pin "2") (pinfunction "2_2") (pintype "passive"))
      (node (ref "R9") (pin "2") (pinfunction "2_2") (pintype "passive"))
      (node (ref "U4") (pin "15") (pinfunction "SDA_15") (pintype "bidirectional"))
      (node (ref "U5") (pin "2") (pinfunction "MOSI/SDA_2") (pintype "bidirectional"))
      (node (ref "U6") (pin "9") (pinfunction "SDA_9") (pintype "passive"))
    )
    (net (code "13") (name "/VALVE1") (class "Default")
      (node (ref "R37") (pin "1") (pinfunction "1_1") (pintype "passive"))
      (node (ref "U4") (pin "6") (pinfunction "P2_6") (pintype "bidirectional"))
    )
    (net (code "14") (name "/VALVE1_IN") (class "Default")
      (node (ref "C29") (pin "2") (pinfunction "2_2") (pintype "passive"))
      (node (ref "R29") (pin "1") (pinfunction "1_1") (pintype "passive"))
      (node (ref "SW4") (pin "1") (pinfunction "1_1") (pintype "passive"))
      (node (ref "SW4") (pin "2") (pinfunction "2_2") (pintype "passive"))
      (node (ref "U4") (pin "9") (pinfunction "P4_9") (pintype "bidirectional"))
    )
    (net (code "15") (name "/VALVE2") (class "Default")
      (node (ref "R38") (pin "1") (pinfunction "1_1") (pintype "passive"))
      (node (ref "U4") (pin "5") (pinfunction "P1_5") (pintype "bidirectional"))
    )
    (net (code "16") (name "/VALVE2_IN") (class "Default")
      (node (ref "C28") (pin "2") (pinfunction "2_2") (pintype "passive"))
      (node (ref "R28") (pin "1") (pinfunction "1_1") (pintype "passive"))
      (node (ref "SW3") (pin "1") (pinfunction "1_1") (pintype "passive"))
      (node (ref "SW3") (pin "2") (pinfunction "2_2") (pintype "passive"))
      (node (ref "U4") (pin "10") (pinfunction "P5_10") (pintype "bidirectional"))
    )
    (net (code "17") (name "3V3") (class "Default")
      (node (ref "C16") (pin "2") (pinfunction "2_2") (pintype "passive"))
      (node (ref "SW5") (pin "1") (pinfunction "1_1") (pintype "passive"))
      (node (ref "U3") (pin "5") (pinfunction "VOUT_5") (pintype "power_in"))
    )
    (net (code "18") (name "4V5") (class "Default")
      (node (ref "C27") (pin "1") (pinfunction "1_1") (pintype "passive"))
      (node (ref "C30") (pin "1") (pinfunction "1_1") (pintype "passive"))
      (node (ref "C4") (pin "2") (pinfunction "2_2") (pintype "passive"))
      (node (ref "C5") (pin "2") (pinfunction "2_2") (pintype "passive"))
      (node (ref "C6") (pin "2") (pinfunction "2_2") (pintype "passive"))
      (node (ref "C7") (pin "2") (pinfunction "2_2") (pintype "passive"))
      (node (ref "D4") (pin "2") (pinfunction "K_2") (pintype "passive"))
      (node (ref "D5") (pin "1") (pinfunction "A_1") (pintype "passive"))
      (node (ref "D6") (pin "2") (pinfunction "K_2") (pintype "passive"))
      (node (ref "D7") (pin "1") (pinfunction "A_1") (pintype "passive"))
      (node (ref "F1") (pin "1") (pinfunction "1_1") (pintype "passive"))
      (node (ref "L1") (pin "2") (pinfunction "2_2") (pintype "passive"))
      (node (ref "R15") (pin "1") (pinfunction "1_1") (pintype "passive"))
      (node (ref "R16") (pin "1") (pinfunction "1_1") (pintype "passive"))
      (node (ref "R17") (pin "1") (pinfunction "1_1") (pintype "passive"))
      (node (ref "R18") (pin "1") (pinfunction "1_1") (pintype "passive"))
      (node (ref "R19") (pin "1") (pinfunction "1_1") (pintype "passive"))
      (node (ref "R2") (pin "2") (pinfunction "2_2") (pintype "passive"))
      (node (ref "U7") (pin "1") (pinfunction "+_1") (pintype "passive"))
      (node (ref "U8") (pin "1") (pinfunction "+_1") (pintype "passive"))
    )
    (net (code "19") (name "4V5A") (class "Default")
      (node (ref "C15") (pin "2") (pinfunction "2_2") (pintype "passive"))
      (node (ref "D2") (pin "1") (pinfunction "A_1") (pintype "passive"))
      (node (ref "F1") (pin "2") (pinfunction "2_2") (pintype "passive"))
      (node (ref "U3") (pin "1") (pinfunction "VIN_1") (pintype "power_in"))
      (node (ref "U3") (pin "3") (pinfunction "EN_3") (pintype "input"))
    )
    (net (code "20") (name "6V") (class "Default")
      (node (ref "C11") (pin "2") (pinfunction "2_2") (pintype "passive"))
      (node (ref "C12") (pin "2") (pinfunction "2_2") (pintype "passive"))
      (node (ref "C13") (pin "2") (pinfunction "2_2") (pintype "passive"))
      (node (ref "C14") (pin "2") (pinfunction "2_2") (pintype "passive"))
      (node (ref "C31") (pin "1") (pinfunction "1_1") (pintype "passive"))
      (node (ref "C32") (pin "1") (pinfunction "1_1") (pintype "passive"))
      (node (ref "D10") (pin "1") (pinfunction "A_1") (pintype "passive"))
      (node (ref "D11") (pin "1") (pinfunction "A_1") (pintype "passive"))
      (node (ref "D8") (pin "2") (pinfunction "K_2") (pintype "passive"))
      (node (ref "D9") (pin "2") (pinfunction "K_2") (pintype "passive"))
      (node (ref "L2") (pin "2") (pinfunction "2_2") (pintype "passive"))
      (node (ref "R5") (pin "2") (pinfunction "2_2") (pintype "passive"))
      (node (ref "U10") (pin "1") (pinfunction "+_1") (pintype "passive"))
      (node (ref "U9") (pin "1") (pinfunction "+_1") (pintype "passive"))
    )
    (net (code "21") (name "D3V3") (class "Default")
      (node (ref "C18") (pin "2") (pinfunction "2_2") (pintype "passive"))
      (node (ref "C19") (pin "1") (pinfunction "1_1") (pintype "passive"))
      (node (ref "C20") (pin "2") (pinfunction "2_2") (pintype "passive"))
      (node (ref "C22") (pin "2") (pinfunction "2_2") (pintype "passive"))
      (node (ref "FB1") (pin "2") (pinfunction "2_2") (pintype "passive"))
      (node (ref "J1") (pin "2") (pinfunction "2_2") (pintype "passive"))
      (node (ref "J2") (pin "2") (pinfunction "2_2") (pintype "passive"))
      (node (ref "J3") (pin "2") (pinfunction "2_2") (pintype "passive"))
      (node (ref "J4") (pin "2") (pinfunction "2_2") (pintype "passive"))
      (node (ref "J5") (pin "2") (pinfunction "2_2") (pintype "passive"))
      (node (ref "JP1") (pin "2") (pinfunction "2_2") (pintype "passive"))
      (node (ref "R10") (pin "1") (pinfunction "1_1") (pintype "passive"))
      (node (ref "R11") (pin "1") (pinfunction "1_1") (pintype "passive"))
      (node (ref "R12") (pin "2") (pinfunction "2_2") (pintype "passive"))
      (node (ref "R13") (pin "2") (pinfunction "2_2") (pintype "passive"))
      (node (ref "R14") (pin "1") (pinfunction "1_1") (pintype "passive"))
      (node (ref "R21") (pin "1") (pinfunction "1_1") (pintype "passive"))
      (node (ref "R22") (pin "1") (pinfunction "1_1") (pintype "passive"))
      (node (ref "R28") (pin "2") (pinfunction "2_2") (pintype "passive"))
      (node (ref "R29") (pin "2") (pinfunction "2_2") (pintype "passive"))
      (node (ref "R8") (pin "1") (pinfunction "1_1") (pintype "passive"))
      (node (ref "R9") (pin "1") (pinfunction "1_1") (pintype "passive"))
      (node (ref "U4") (pin "1") (pinfunction "A0_1") (pintype "input"))
      (node (ref "U4") (pin "16") (pinfunction "VCC_16") (pintype "power_in"))
      (node (ref "U4") (pin "2") (pinfunction "A1_2") (pintype "input"))
      (node (ref "U4") (pin "3") (pinfunction "A2_3") (pintype "input"))
      (node (ref "U6") (pin "10") (pinfunction "VDD_10") (pintype "power_in"))
      (node (ref "U6") (pin "5") (pinfunction "A0_5") (pintype "bidirectional"))
    )
    (net (code "22") (name "GND") (class "Default")
      (node (ref "C10") (pin "1") (pinfunction "1_1") (pintype "passive"))
      (node (ref "C12") (pin "1") (pinfunction "1_1") (pintype "passive"))
      (node (ref "C13") (pin "1") (pinfunction "1_1") (pintype "passive"))
      (node (ref "C14") (pin "1") (pinfunction "1_1") (pintype "passive"))
      (node (ref "C15") (pin "1") (pinfunction "1_1") (pintype "passive"))
      (node (ref "C16") (pin "1") (pinfunction "1_1") (pintype "passive"))
      (node (ref "C17") (pin "1") (pinfunction "1_1") (pintype "passive"))
      (node (ref "C18") (pin "1") (pinfunction "1_1") (pintype "passive"))
      (node (ref "C19") (pin "2") (pinfunction "2_2") (pintype "passive"))
      (node (ref "C2") (pin "1") (pinfunction "1_1") (pintype "passive"))
      (node (ref "C20") (pin "1") (pinfunction "1_1") (pintype "passive"))
      (node (ref "C22") (pin "1") (pinfunction "1_1") (pintype "passive"))
      (node (ref "C23") (pin "1") (pinfunction "1_1") (pintype "passive"))
      (node (ref "C24") (pin "1") (pinfunction "1_1") (pintype "passive"))
      (node (ref "C27") (pin "2") (pinfunction "2_2") (pintype "passive"))
      (node (ref "C28") (pin "1") (pinfunction "1_1") (pintype "passive"))
      (node (ref "C29") (pin "1") (pinfunction "1_1") (pintype "passive"))
      (node (ref "C3") (pin "1") (pinfunction "1_1") (pintype "passive"))
      (node (ref "C30") (pin "2") (pinfunction "2_2") (pintype "passive"))
      (node (ref "C31") (pin "2") (pinfunction "2_2") (pintype "passive"))
      (node (ref "C32") (pin "2") (pinfunction "2_2") (pintype "passive"))
      (node (ref "C5") (pin "1") (pinfunction "1_1") (pintype "passive"))
      (node (ref "C6") (pin "1") (pinfunction "1_1") (pintype "passive"))
      (node (ref "C7") (pin "1") (pinfunction "1_1") (pintype "passive"))
      (node (ref "C9") (pin "1") (pinfunction "1_1") (pintype "passive"))
      (node (ref "D3") (pin "2") (pinfunction "K_2") (pintype "passive"))
      (node (ref "J1") (pin "1") (pinfunction "1_1") (pintype "passive"))
      (node (ref "J2") (pin "1") (pinfunction "1_1") (pintype "passive"))
      (node (ref "J3") (pin "1") (pinfunction "1_1") (pintype "passive"))
      (node (ref "J4") (pin "1") (pinfunction "1_1") (pintype "passive"))
      (node (ref "J5") (pin "1") (pinfunction "1_1") (pintype "passive"))
      (node (ref "JDC1") (pin "2") (pinfunction "TN_2") (pintype "passive"))
      (node (ref "JDC1") (pin "3") (pinfunction "S_3") (pintype "power_in"))
      (node (ref "Q3") (pin "2") (pinfunction "S_2") (pintype "passive"))
      (node (ref "Q4") (pin "2") (pinfunction "S_2") (pintype "passive"))
      (node (ref "Q5") (pin "2") (pinfunction "S_2") (pintype "passive"))
      (node (ref "Q6") (pin "2") (pinfunction "S_2") (pintype "passive"))
      (node (ref "R3") (pin "1") (pinfunction "1_1") (pintype "passive"))
      (node (ref "R31") (pin "1") (pinfunction "1_1") (pintype "passive"))
      (node (ref "R34") (pin "1") (pinfunction "1_1") (pintype "passive"))
      (node (ref "R39") (pin "1") (pinfunction "1_1") (pintype "passive"))
      (node (ref "R40") (pin "1") (pinfunction "1_1") (pintype "passive"))
      (node (ref "R6") (pin "1") (pinfunction "1_1") (pintype "passive"))
      (node (ref "R7") (pin "2") (pinfunction "2_2") (pintype "passive"))
      (node (ref "SW1") (pin "3") (pinfunction "3_3") (pintype "passive"))
      (node (ref "SW1") (pin "4") (pinfunction "4_4") (pintype "passive"))
      (node (ref "SW2") (pin "3") (pinfunction "3_3") (pintype "passive"))
      (node (ref "SW2") (pin "4") (pinfunction "4_4") (pintype "passive"))
      (node (ref "SW3") (pin "3") (pinfunction "3_3") (pintype "passive"))
      (node (ref "SW3") (pin "4") (pinfunction "4_4") (pintype "passive"))
      (node (ref "SW4") (pin "3") (pinfunction "3_3") (pintype "passive"))
      (node (ref "SW4") (pin "4") (pinfunction "4_4") (pintype "passive"))
      (node (ref "U1") (pin "3") (pinfunction "GND_3") (pintype "power_in"))
      (node (ref "U11") (pin "2") (pinfunction "EMITTER_2") (pintype "passive"))
      (node (ref "U12") (pin "2") (pinfunction "EMITTER_2") (pintype "passive"))
      (node (ref "U2") (pin "3") (pinfunction "GND_3") (pintype "power_in"))
      (node (ref "U3") (pin "2") (pinfunction "GND_2") (pintype "power_in"))
      (node (ref "U4") (pin "8") (pinfunction "GND_8") (pintype "power_in"))
      (node (ref "U5") (pin "10") (pinfunction "VSS_10") (pintype "power_in"))
      (node (ref "U6") (pin "6") (pinfunction "VSS_6") (pintype "power_in"))
      (node (ref "U6") (pin "7") (pinfunction "A1_7") (pintype "bidirectional"))
    )
    (net (code "23") (name "Net-(C17-Pad2)") (class "Default")
      (node (ref "C17") (pin "2") (pinfunction "2_2") (pintype "passive"))
      (node (ref "FB1") (pin "1") (pinfunction "1_1") (pintype "passive"))
      (node (ref "SW5") (pin "2") (pinfunction "2_2") (pintype "passive"))
    )
    (net (code "24") (name "Net-(D2-K)") (class "Default")
      (node (ref "D2") (pin "2") (pinfunction "K_2") (pintype "passive"))
      (node (ref "R7") (pin "1") (pinfunction "1_1") (pintype "passive"))
    )
    (net (code "25") (name "Net-(D3-A)") (class "Default")
      (node (ref "D3") (pin "1") (pinfunction "A_1") (pintype "passive"))
      (node (ref "R14") (pin "2") (pinfunction "2_2") (pintype "passive"))
    )
    (net (code "26") (name "Net-(D4-A)") (class "Default")
      (node (ref "D4") (pin "1") (pinfunction "A_1") (pintype "passive"))
      (node (ref "R27") (pin "2") (pinfunction "2_2") (pintype "passive"))
    )
    (net (code "27") (name "Net-(D5-K)") (class "Default")
      (node (ref "D5") (pin "2") (pinfunction "K_2") (pintype "passive"))
      (node (ref "Q3") (pin "3") (pinfunction "D_3") (pintype "passive"))
      (node (ref "R27") (pin "1") (pinfunction "1_1") (pintype "passive"))
      (node (ref "U7") (pin "2") (pinfunction "-_2") (pintype "passive"))
    )
    (net (code "28") (name "Net-(D6-A)") (class "Default")
      (node (ref "D6") (pin "1") (pinfunction "A_1") (pintype "passive"))
      (node (ref "R32") (pin "2") (pinfunction "2_2") (pintype "passive"))
    )
    (net (code "29") (name "Net-(D7-K)") (class "Default")
      (node (ref "D7") (pin "2") (pinfunction "K_2") (pintype "passive"))
      (node (ref "Q4") (pin "3") (pinfunction "D_3") (pintype "passive"))
      (node (ref "R32") (pin "1") (pinfunction "1_1") (pintype "passive"))
      (node (ref "U8") (pin "2") (pinfunction "-_2") (pintype "passive"))
    )
    (net (code "30") (name "Net-(D8-A)") (class "Default")
      (node (ref "D8") (pin "1") (pinfunction "A_1") (pintype "passive"))
      (node (ref "R35") (pin "2") (pinfunction "2_2") (pintype "passive"))
    )
    (net (code "31") (name "Net-(D9-A)") (class "Default")
      (node (ref "D9") (pin "1") (pinfunction "A_1") (pintype "passive"))
      (node (ref "R36") (pin "2") (pinfunction "2_2") (pintype "passive"))
    )
    (net (code "32") (name "Net-(D10-K)") (class "Default")
      (node (ref "D10") (pin "2") (pinfunction "K_2") (pintype "passive"))
      (node (ref "Q6") (pin "3") (pinfunction "D_3") (pintype "passive"))
      (node (ref "R35") (pin "1") (pinfunction "1_1") (pintype "passive"))
      (node (ref "U9") (pin "2") (pinfunction "-_2") (pintype "passive"))
    )
    (net (code "33") (name "Net-(D11-K)") (class "Default")
      (node (ref "D11") (pin "2") (pinfunction "K_2") (pintype "passive"))
      (node (ref "Q5") (pin "3") (pinfunction "D_3") (pintype "passive"))
      (node (ref "R36") (pin "1") (pinfunction "1_1") (pintype "passive"))
      (node (ref "U10") (pin "2") (pinfunction "-_2") (pintype "passive"))
    )
    (net (code "34") (name "Net-(LED1-Pad1)") (class "Default")
      (node (ref "LED1") (pin "1") (pinfunction "1_1") (pintype "passive"))
      (node (ref "R20") (pin "2") (pinfunction "2_2") (pintype "passive"))
    )
    (net (code "35") (name "Net-(LED2-Pad2)") (class "Default")
      (node (ref "LED2") (pin "2") (pinfunction "2_2") (pintype "passive"))
      (node (ref "R15") (pin "2") (pinfunction "2_2") (pintype "passive"))
    )
    (net (code "36") (name "Net-(LED3-Pad2)") (class "Default")
      (node (ref "LED3") (pin "2") (pinfunction "2_2") (pintype "passive"))
      (node (ref "R16") (pin "2") (pinfunction "2_2") (pintype "passive"))
    )
    (net (code "37") (name "Net-(LED4-Pad2)") (class "Default")
      (node (ref "LED4") (pin "2") (pinfunction "2_2") (pintype "passive"))
      (node (ref "R17") (pin "2") (pinfunction "2_2") (pintype "passive"))
    )
    (net (code "38") (name "Net-(LED5-Pad2)") (class "Default")
      (node (ref "LED5") (pin "2") (pinfunction "2_2") (pintype "passive"))
      (node (ref "R18") (pin "2") (pinfunction "2_2") (pintype "passive"))
    )
    (net (code "39") (name "Net-(LED6-Pad2)") (class "Default")
      (node (ref "LED6") (pin "2") (pinfunction "2_2") (pintype "passive"))
      (node (ref "R19") (pin "2") (pinfunction "2_2") (pintype "passive"))
    )
    (net (code "40") (name "Net-(Q3-G)") (class "Default")
      (node (ref "Q3") (pin "1") (pinfunction "G_1") (pintype "passive"))
      (node (ref "R30") (pin "2") (pinfunction "2_2") (pintype "passive"))
      (node (ref "R31") (pin "2") (pinfunction "2_2") (pintype "passive"))
    )
    (net (code "41") (name "Net-(Q4-G)") (class "Default")
      (node (ref "Q4") (pin "1") (pinfunction "G_1") (pintype "passive"))
      (node (ref "R33") (pin "2") (pinfunction "2_2") (pintype "passive"))
      (node (ref "R34") (pin "2") (pinfunction "2_2") (pintype "passive"))
    )
    (net (code "42") (name "Net-(Q5-G)") (class "Default")
      (node (ref "Q5") (pin "1") (pinfunction "G_1") (pintype "passive"))
      (node (ref "R37") (pin "2") (pinfunction "2_2") (pintype "passive"))
      (node (ref "R39") (pin "2") (pinfunction "2_2") (pintype "passive"))
    )
    (net (code "43") (name "Net-(Q6-G)") (class "Default")
      (node (ref "Q6") (pin "1") (pinfunction "G_1") (pintype "passive"))
      (node (ref "R38") (pin "2") (pinfunction "2_2") (pintype "passive"))
      (node (ref "R40") (pin "2") (pinfunction "2_2") (pintype "passive"))
    )
    (net (code "44") (name "Net-(TP1-TP)") (class "Default")
      (node (ref "R8") (pin "2") (pinfunction "2_2") (pintype "passive"))
      (node (ref "TP1") (pin "1") (pinfunction "TP_1") (pintype "passive"))
      (node (ref "U4") (pin "13") (pinfunction "/INT_13") (pintype "output"))
    )
    (net (code "45") (name "Net-(TP3-TP)") (class "Default")
      (node (ref "TP3") (pin "1") (pinfunction "TP_1") (pintype "passive"))
      (node (ref "U5") (pin "8") (pinfunction "EOC_8") (pintype "output"))
    )
    (net (code "46") (name "Net-(U1-BST)") (class "Default")
      (node (ref "C1") (pin "2") (pinfunction "2_2") (pintype "passive"))
      (node (ref "U1") (pin "4") (pinfunction "BST_4") (pintype "passive"))
    )
    (net (code "47") (name "Net-(U1-EN)") (class "Default")
      (node (ref "R1") (pin "1") (pinfunction "1_1") (pintype "passive"))
      (node (ref "U1") (pin "5") (pinfunction "EN_5") (pintype "passive"))
    )
    (net (code "48") (name "Net-(U1-FB)") (class "Default")
      (node (ref "C4") (pin "1") (pinfunction "1_1") (pintype "passive"))
      (node (ref "R2") (pin "1") (pinfunction "1_1") (pintype "passive"))
      (node (ref "R3") (pin "2") (pinfunction "2_2") (pintype "passive"))
      (node (ref "U1") (pin "6") (pinfunction "FB_6") (pintype "passive"))
    )
    (net (code "49") (name "Net-(U1-SW)") (class "Default")
      (node (ref "C1") (pin "1") (pinfunction "1_1") (pintype "passive"))
      (node (ref "L1") (pin "1") (pinfunction "1_1") (pintype "passive"))
      (node (ref "U1") (pin "2") (pinfunction "SW_2") (pintype "passive"))
    )
    (net (code "50") (name "Net-(U2-BST)") (class "Default")
      (node (ref "C8") (pin "2") (pinfunction "2_2") (pintype "passive"))
      (node (ref "U2") (pin "4") (pinfunction "BST_4") (pintype "passive"))
    )
    (net (code "51") (name "Net-(U2-EN)") (class "Default")
      (node (ref "R4") (pin "1") (pinfunction "1_1") (pintype "passive"))
      (node (ref "U2") (pin "5") (pinfunction "EN_5") (pintype "passive"))
    )
    (net (code "52") (name "Net-(U2-FB)") (class "Default")
      (node (ref "C11") (pin "1") (pinfunction "1_1") (pintype "passive"))
      (node (ref "R5") (pin "1") (pinfunction "1_1") (pintype "passive"))
      (node (ref "R6") (pin "2") (pinfunction "2_2") (pintype "passive"))
      (node (ref "U2") (pin "6") (pinfunction "FB_6") (pintype "passive"))
    )
    (net (code "53") (name "Net-(U2-SW)") (class "Default")
      (node (ref "C8") (pin "1") (pinfunction "1_1") (pintype "passive"))
      (node (ref "L2") (pin "1") (pinfunction "1_1") (pintype "passive"))
      (node (ref "U2") (pin "2") (pinfunction "SW_2") (pintype "passive"))
    )
    (net (code "54") (name "Net-(U5-VDD)") (class "Default")
      (node (ref "JP1") (pin "1") (pinfunction "1_1") (pintype "passive"))
      (node (ref "U5") (pin "12") (pinfunction "VDD_12") (pintype "power_in"))
    )
    (net (code "55") (name "Net-(U5-VO+)") (class "Default")
      (node (ref "C21") (pin "2") (pinfunction "2_2") (pintype "passive"))
      (node (ref "U5") (pin "4") (pinfunction "VO+_4") (pintype "output"))
    )
    (net (code "56") (name "Net-(U5-VO-)") (class "Default")
      (node (ref "C21") (pin "1") (pinfunction "1_1") (pintype "passive"))
      (node (ref "U5") (pin "6") (pinfunction "VO-_6") (pintype "output"))
    )
    (net (code "57") (name "Net-(U11-BASE)") (class "Default")
      (node (ref "R25") (pin "2") (pinfunction "2_2") (pintype "passive"))
      (node (ref "U11") (pin "1") (pinfunction "BASE_1") (pintype "passive"))
    )
    (net (code "58") (name "Net-(U11-COLLECTOR)") (class "Default")
      (node (ref "LED1") (pin "2") (pinfunction "2_2") (pintype "passive"))
      (node (ref "U11") (pin "3") (pinfunction "COLLECTOR_3") (pintype "passive"))
    )
    (net (code "59") (name "Net-(U12-BASE)") (class "Default")
      (node (ref "R23") (pin "1") (pinfunction "1_1") (pintype "passive"))
      (node (ref "U12") (pin "1") (pinfunction "BASE_1") (pintype "passive"))
    )
    (net (code "60") (name "Net-(U12-COLLECTOR)") (class "Default")
      (node (ref "LED2") (pin "1") (pinfunction "1_1") (pintype "passive"))
      (node (ref "LED3") (pin "1") (pinfunction "1_1") (pintype "passive"))
      (node (ref "LED4") (pin "1") (pinfunction "1_1") (pintype "passive"))
      (node (ref "U12") (pin "3") (pinfunction "COLLECTOR_3") (pintype "passive"))
    )
    (net (code "61") (name "VIN") (class "Default")
      (node (ref "C10") (pin "2") (pinfunction "2_2") (pintype "passive"))
      (node (ref "C2") (pin "2") (pinfunction "2_2") (pintype "passive"))
      (node (ref "C3") (pin "2") (pinfunction "2_2") (pintype "passive"))
      (node (ref "C9") (pin "2") (pinfunction "2_2") (pintype "passive"))
      (node (ref "D1") (pin "2") (pinfunction "K_2") (pintype "passive"))
      (node (ref "R1") (pin "2") (pinfunction "2_2") (pintype "passive"))
      (node (ref "R20") (pin "1") (pinfunction "1_1") (pintype "passive"))
      (node (ref "R4") (pin "2") (pinfunction "2_2") (pintype "passive"))
      (node (ref "U1") (pin "1") (pinfunction "IN_1") (pintype "power_in"))
      (node (ref "U2") (pin "1") (pinfunction "IN_1") (pintype "power_in"))
    )
    (net (code "62") (name "unconnected-(U5-MISO-Pad7)") (class "Default")
      (node (ref "U5") (pin "7") (pinfunction "MISO_7") (pintype "output+no_connect"))
    )
    (net (code "63") (name "unconnected-(U5-SS-Pad1)") (class "Default")
      (node (ref "U5") (pin "1") (pinfunction "SS_1") (pintype "input+no_connect"))
    )
  )
)
